# ctrl-pico.net
KiCad netlist of a schematic drawn in EAGLE
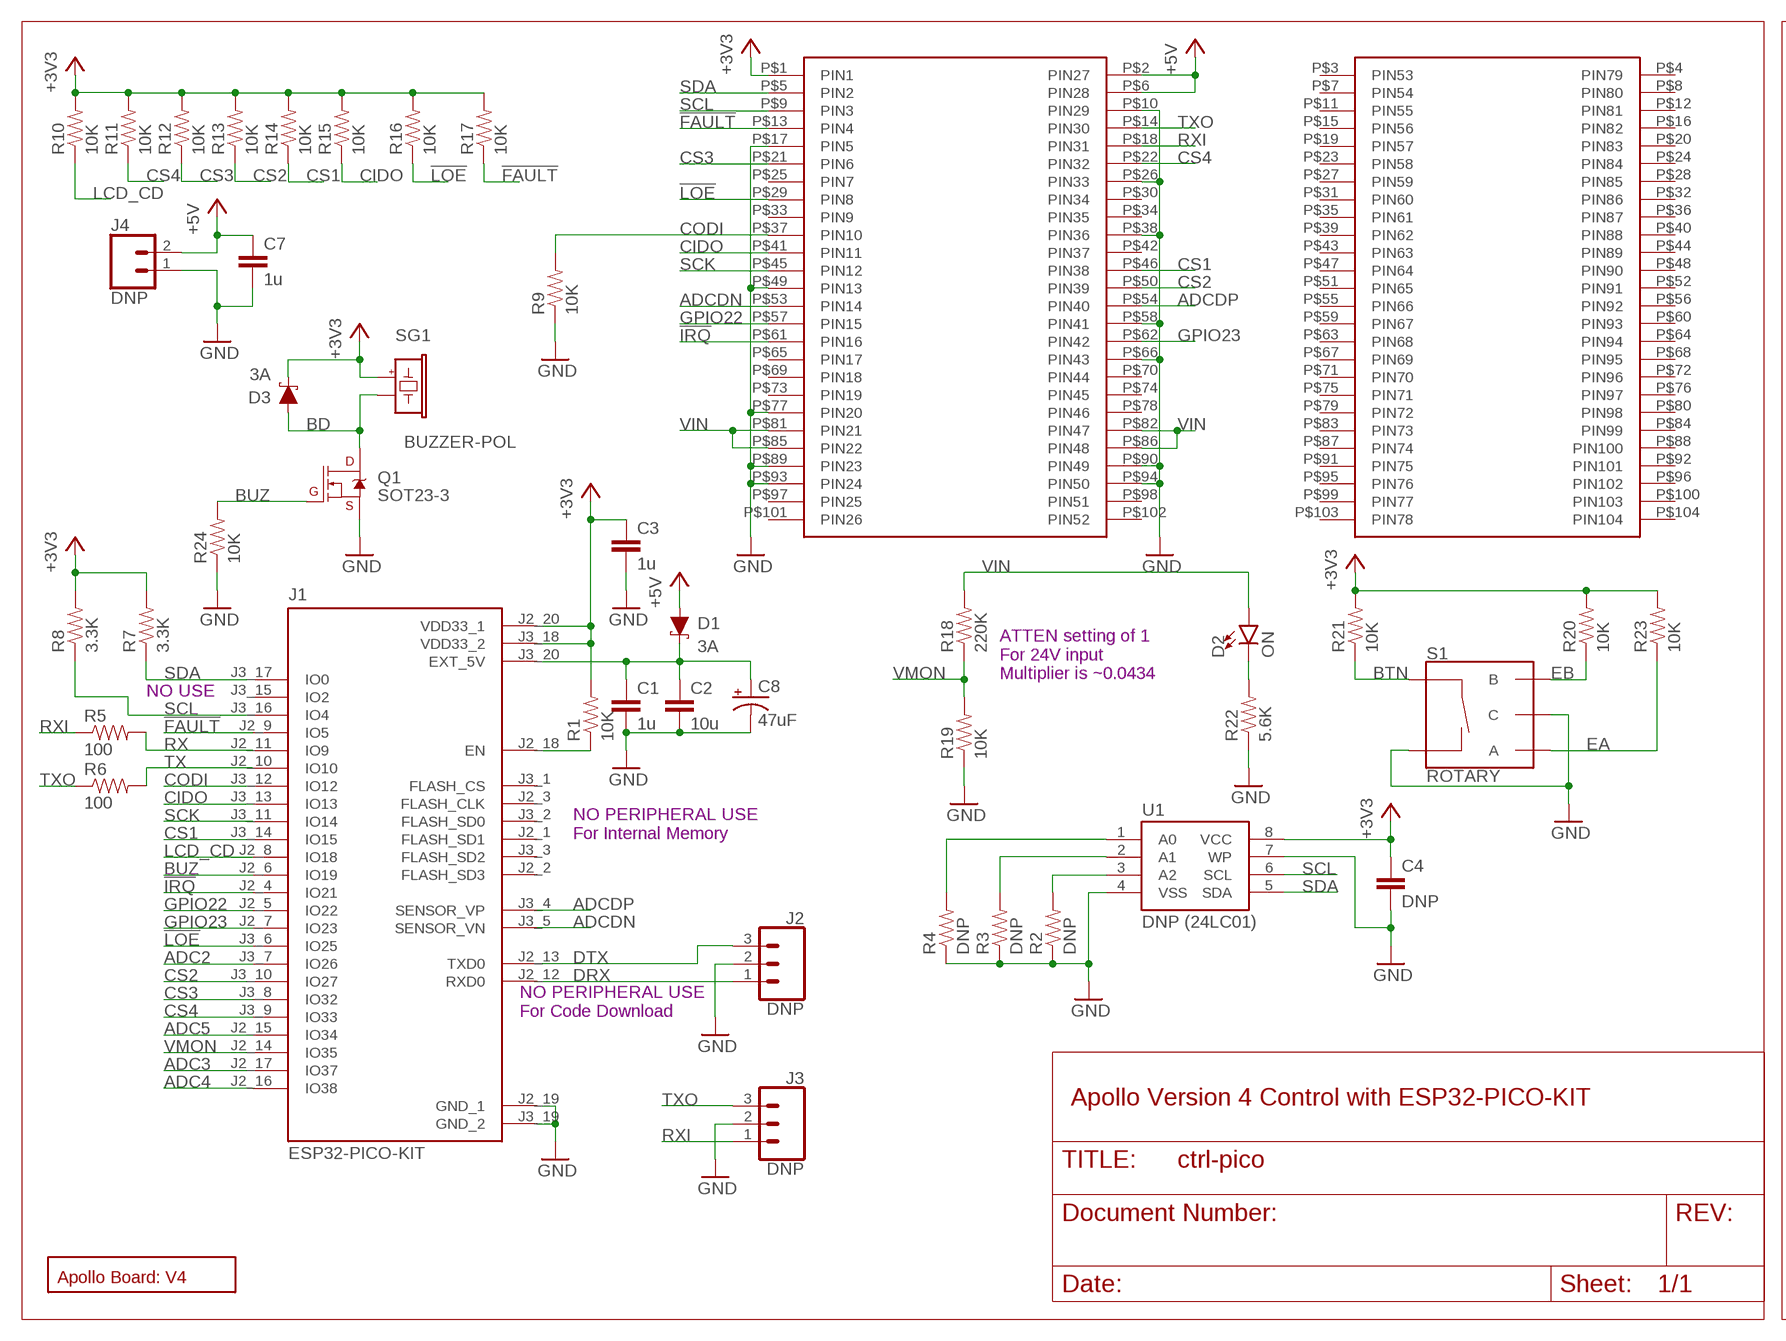
[diagram p0: schematic, sheet 1, part 1 of 2]
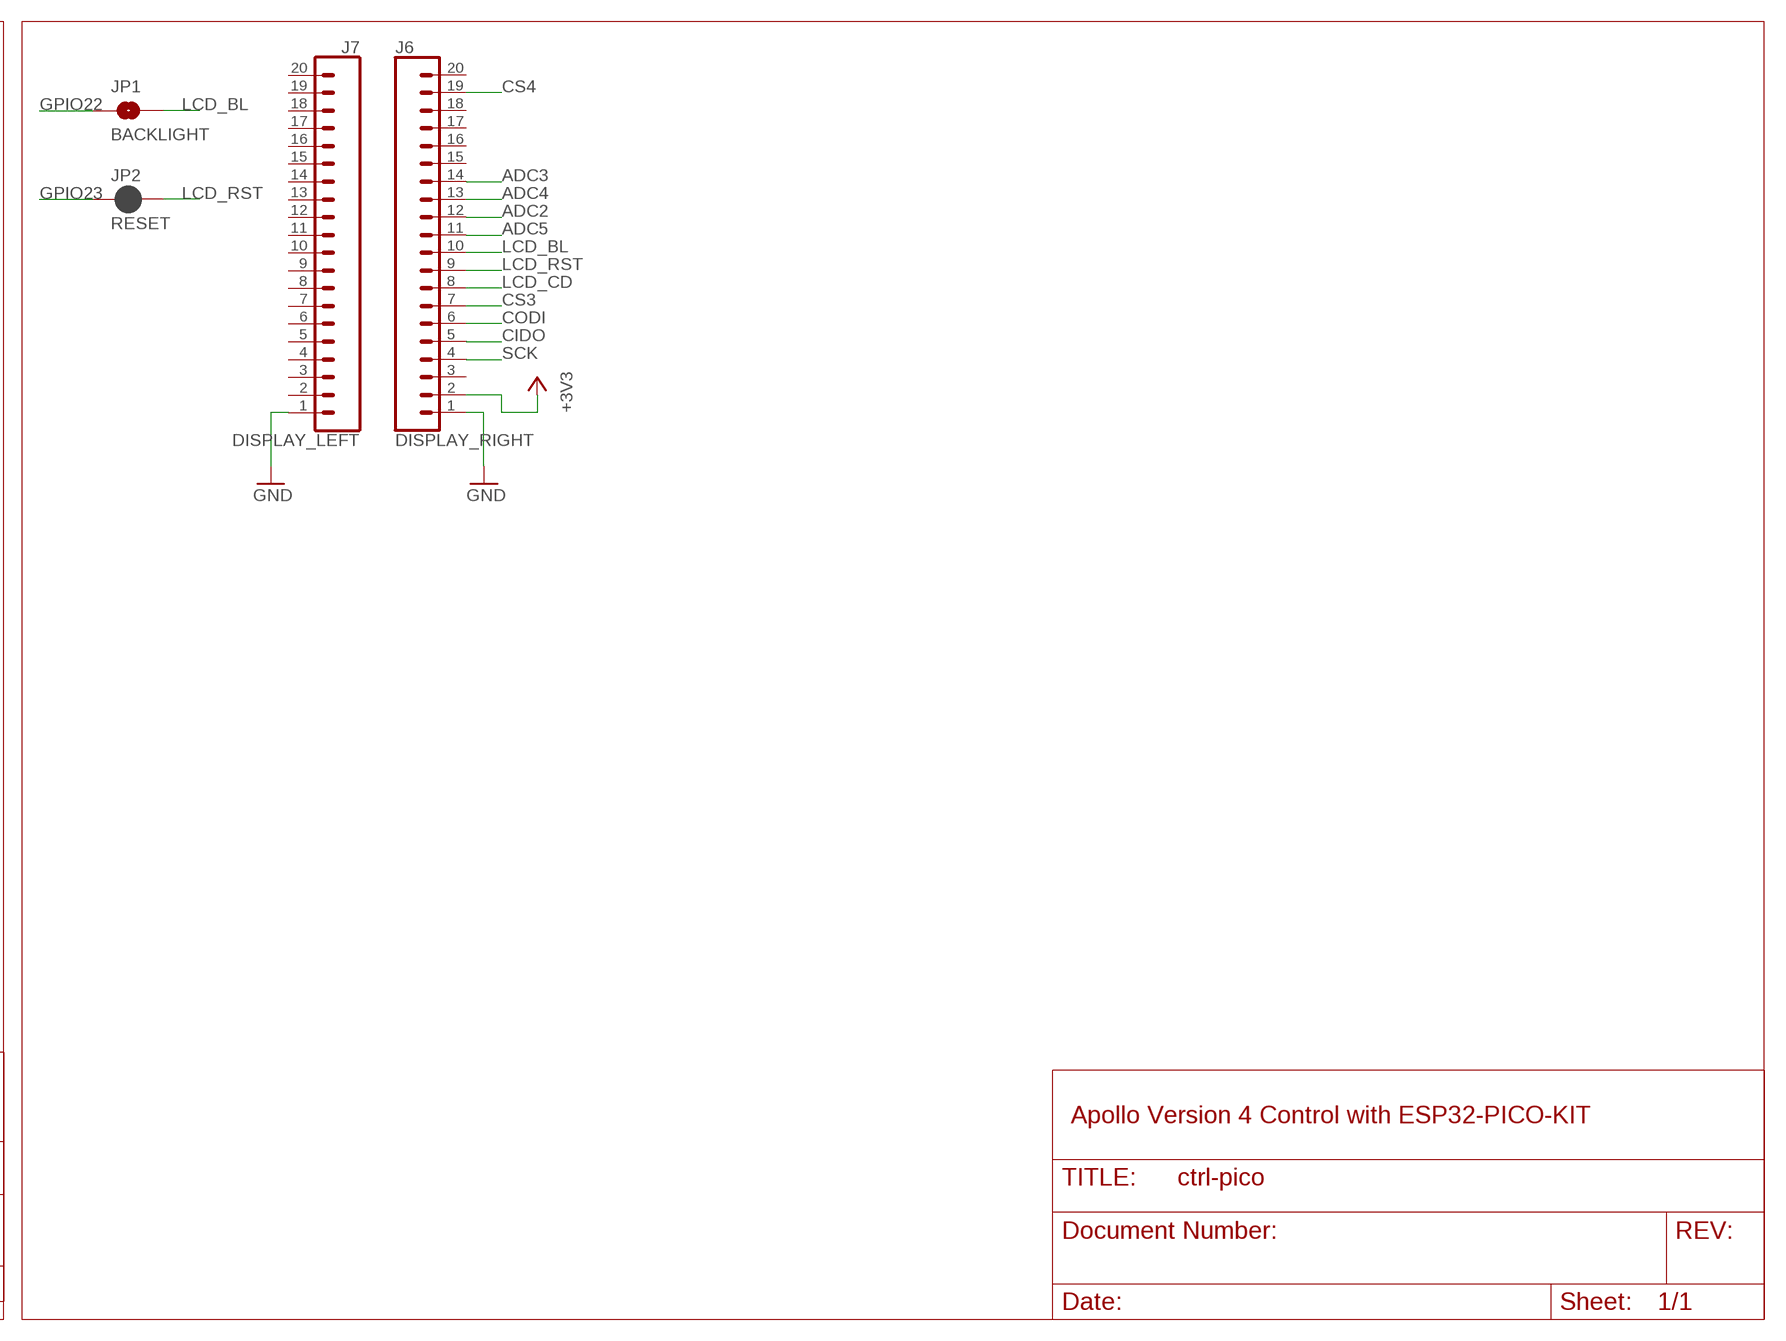
[diagram p1: schematic, sheet 1, part 2 of 2]

(export (version "E")
  (design (tool "Eeschema 10.0.6"))
  (components
    (comp (ref "C1")
      (value "1u")
      (footprint "eagle-import:0805")
      (libsource (lib "eagle-import") (part "CAP0805"))
    )
    (comp (ref "C2")
      (value "10u")
      (footprint "eagle-import:0805")
      (libsource (lib "eagle-import") (part "CAP0805"))
    )
    (comp (ref "C3")
      (value "1u")
      (footprint "eagle-import:0805")
      (libsource (lib "eagle-import") (part "CAP0805"))
    )
    (comp (ref "C4")
      (value "DNP")
      (footprint "eagle-import:0805")
      (libsource (lib "eagle-import") (part "CAP0805"))
    )
    (comp (ref "C7")
      (value "1u")
      (footprint "eagle-import:0805")
      (libsource (lib "eagle-import") (part "CAP0805"))
    )
    (comp (ref "C8")
      (value "47uF")
      (footprint "eagle-import:PANASONIC_D")
      (libsource (lib "eagle-import") (part "47UF-POLAR-PANASONIC_D-35V-20%"))
    )
    (comp (ref "D1")
      (value "3A")
      (footprint "eagle-import:SMA-DIODE")
      (libsource (lib "eagle-import") (part "DIODE-SCHOTTKY-B340A"))
    )
    (comp (ref "D2")
      (value "ON")
      (footprint "eagle-import:LED-0603")
      (libsource (lib "eagle-import") (part "LED-GREEN0603"))
    )
    (comp (ref "D3")
      (value "3A")
      (footprint "eagle-import:SMA-DIODE")
      (libsource (lib "eagle-import") (part "DIODE-SCHOTTKY-B340A"))
    )
    (comp (ref "J1")
      (value "ESP32-PICO-KIT")
      (footprint "eagle-import:XCVR_ESP32-PICO-KIT")
      (fields (field (name "DIGI-KEY_PART_NUMBER") "1965-1004-ND") (field (name "MF") "Espressif Systems"))
      (libsource (lib "eagle-import") (part "ESP32-PICO-KIT"))
    )
    (comp (ref "J2")
      (value "DNP")
      (footprint "eagle-import:1X03")
      (libsource (lib "eagle-import") (part "CONN_03"))
    )
    (comp (ref "J3")
      (value "DNP")
      (footprint "eagle-import:1X03")
      (libsource (lib "eagle-import") (part "CONN_03"))
    )
    (comp (ref "J4")
      (value "DNP")
      (footprint "eagle-import:1X02")
      (libsource (lib "eagle-import") (part "CONN_02"))
    )
    (comp (ref "J6")
      (value "DISPLAY_RIGHT")
      (footprint "eagle-import:1X20")
      (libsource (lib "eagle-import") (part "CONN_20"))
    )
    (comp (ref "J7")
      (value "DISPLAY_LEFT")
      (footprint "eagle-import:1X20")
      (libsource (lib "eagle-import") (part "CONN_20"))
    )
    (comp (ref "JP1")
      (value "BACKLIGHT")
      (footprint "eagle-import:SMT-JUMPER_2_NO_NO-SILK")
      (libsource (lib "eagle-import") (part "JUMPER-SMT_2_NO_NO-SILK"))
    )
    (comp (ref "JP2")
      (value "RESET")
      (footprint "eagle-import:SMT-JUMPER_2_NC_PASTE_NO-SILK")
      (libsource (lib "eagle-import") (part "JUMPER-SMT_2_NC_PASTE_NO-SILK"))
    )
    (comp (ref "Q1")
      (value "SOT23-3")
      (footprint "eagle-import:SOT23-3")
      (libsource (lib "eagle-import") (part "MOSFET-NCH-AO3404A"))
    )
    (comp (ref "R1")
      (value "10K")
      (footprint "eagle-import:0805")
      (libsource (lib "eagle-import") (part "RESISTOR0805-RES"))
    )
    (comp (ref "R2")
      (value "DNP")
      (footprint "eagle-import:0805")
      (libsource (lib "eagle-import") (part "RESISTOR0805-RES"))
    )
    (comp (ref "R3")
      (value "DNP")
      (footprint "eagle-import:0805")
      (libsource (lib "eagle-import") (part "RESISTOR0805-RES"))
    )
    (comp (ref "R4")
      (value "DNP")
      (footprint "eagle-import:0805")
      (libsource (lib "eagle-import") (part "RESISTOR0805-RES"))
    )
    (comp (ref "R5")
      (value "100")
      (footprint "eagle-import:0805")
      (libsource (lib "eagle-import") (part "RESISTOR0805-RES"))
    )
    (comp (ref "R6")
      (value "100")
      (footprint "eagle-import:0805")
      (libsource (lib "eagle-import") (part "RESISTOR0805-RES"))
    )
    (comp (ref "R7")
      (value "3.3K")
      (footprint "eagle-import:0805")
      (libsource (lib "eagle-import") (part "RESISTOR0805-RES"))
    )
    (comp (ref "R8")
      (value "3.3K")
      (footprint "eagle-import:0805")
      (libsource (lib "eagle-import") (part "RESISTOR0805-RES"))
    )
    (comp (ref "R9")
      (value "10K")
      (footprint "eagle-import:0805")
      (libsource (lib "eagle-import") (part "RESISTOR0805-RES"))
    )
    (comp (ref "R10")
      (value "10K")
      (footprint "eagle-import:0805")
      (libsource (lib "eagle-import") (part "RESISTOR0805-RES"))
    )
    (comp (ref "R11")
      (value "10K")
      (footprint "eagle-import:0805")
      (libsource (lib "eagle-import") (part "RESISTOR0805-RES"))
    )
    (comp (ref "R12")
      (value "10K")
      (footprint "eagle-import:0805")
      (libsource (lib "eagle-import") (part "RESISTOR0805-RES"))
    )
    (comp (ref "R13")
      (value "10K")
      (footprint "eagle-import:0805")
      (libsource (lib "eagle-import") (part "RESISTOR0805-RES"))
    )
    (comp (ref "R14")
      (value "10K")
      (footprint "eagle-import:0805")
      (libsource (lib "eagle-import") (part "RESISTOR0805-RES"))
    )
    (comp (ref "R15")
      (value "10K")
      (footprint "eagle-import:0805")
      (libsource (lib "eagle-import") (part "RESISTOR0805-RES"))
    )
    (comp (ref "R16")
      (value "10K")
      (footprint "eagle-import:0805")
      (libsource (lib "eagle-import") (part "RESISTOR0805-RES"))
    )
    (comp (ref "R17")
      (value "10K")
      (footprint "eagle-import:0805")
      (libsource (lib "eagle-import") (part "RESISTOR0805-RES"))
    )
    (comp (ref "R18")
      (value "220K")
      (footprint "eagle-import:0805")
      (libsource (lib "eagle-import") (part "RESISTOR0805-RES"))
    )
    (comp (ref "R19")
      (value "10K")
      (footprint "eagle-import:0805")
      (libsource (lib "eagle-import") (part "RESISTOR0805-RES"))
    )
    (comp (ref "R20")
      (value "10K")
      (footprint "eagle-import:0805")
      (libsource (lib "eagle-import") (part "RESISTOR0805-RES"))
    )
    (comp (ref "R21")
      (value "10K")
      (footprint "eagle-import:0805")
      (libsource (lib "eagle-import") (part "RESISTOR0805-RES"))
    )
    (comp (ref "R22")
      (value "5.6K")
      (footprint "eagle-import:0805")
      (libsource (lib "eagle-import") (part "RESISTOR0805-RES"))
    )
    (comp (ref "R23")
      (value "10K")
      (footprint "eagle-import:0805")
      (libsource (lib "eagle-import") (part "RESISTOR0805-RES"))
    )
    (comp (ref "R24")
      (value "10K")
      (footprint "eagle-import:0805")
      (libsource (lib "eagle-import") (part "RESISTOR0805-RES"))
    )
    (comp (ref "S1")
      (value "ROTARY")
      (footprint "eagle-import:ROTARY_ENC_PLAIN")
      (libsource (lib "eagle-import") (part "ENCODER-SWITCH"))
    )
    (comp (ref "SG1")
      (value "BUZZER-POL")
      (footprint "eagle-import:BUZZER-SMT-4")
      (libsource (lib "eagle-import") (part "BUZZER-POL"))
    )
    (comp (ref "U$1")
      (value "PC104_CONNECTOR")
      (footprint "eagle-import:PC104_CONNECTOR")
      (libsource (lib "eagle-import") (part "PC104_CONNECTOR"))
    )
    (comp (ref "U$2")
      (value "BOARD_TEMPLATE1")
      (footprint "eagle-import:BOARD_TEMPLATE")
      (libsource (lib "eagle-import") (part "BOARD_TEMPLATE1"))
    )
    (comp (ref "U1")
      (value "DNP (24LC01)")
      (footprint "eagle-import:SO08")
      (libsource (lib "eagle-import") (part "EEPROM-I2CSMD"))
    )
  )
  (nets
    (net (code "1") (name "+3V3") (class "Default")
      (node (ref "C3") (pin "1") (pinfunction "1_1") (pintype "passive"))
      (node (ref "C4") (pin "1") (pinfunction "1_1") (pintype "passive"))
      (node (ref "D3") (pin "C") (pinfunction "C_C") (pintype "passive"))
      (node (ref "J1") (pin "J2_20") (pinfunction "VDD33_1_J2_20") (pintype "power_in"))
      (node (ref "J1") (pin "J3_18") (pinfunction "VDD33_2_J3_18") (pintype "power_in"))
      (node (ref "J6") (pin "2") (pinfunction "2_2") (pintype "passive"))
      (node (ref "R1") (pin "2") (pinfunction "2_2") (pintype "passive"))
      (node (ref "R10") (pin "2") (pinfunction "2_2") (pintype "passive"))
      (node (ref "R11") (pin "2") (pinfunction "2_2") (pintype "passive"))
      (node (ref "R12") (pin "2") (pinfunction "2_2") (pintype "passive"))
      (node (ref "R13") (pin "2") (pinfunction "2_2") (pintype "passive"))
      (node (ref "R14") (pin "2") (pinfunction "2_2") (pintype "passive"))
      (node (ref "R15") (pin "2") (pinfunction "2_2") (pintype "passive"))
      (node (ref "R16") (pin "2") (pinfunction "2_2") (pintype "passive"))
      (node (ref "R17") (pin "2") (pinfunction "2_2") (pintype "passive"))
      (node (ref "R20") (pin "2") (pinfunction "2_2") (pintype "passive"))
      (node (ref "R21") (pin "2") (pinfunction "2_2") (pintype "passive"))
      (node (ref "R23") (pin "2") (pinfunction "2_2") (pintype "passive"))
      (node (ref "R7") (pin "2") (pinfunction "2_2") (pintype "passive"))
      (node (ref "R8") (pin "2") (pinfunction "2_2") (pintype "passive"))
      (node (ref "SG1") (pin "BP") (pinfunction "P_BP") (pintype "passive"))
      (node (ref "U$1") (pin "P$1") (pinfunction "PIN1_P$1") (pintype "bidirectional"))
      (node (ref "U1") (pin "8") (pinfunction "VCC_8") (pintype "power_in"))
    )
    (net (code "2") (name "+5V") (class "Default")
      (node (ref "C7") (pin "1") (pinfunction "1_1") (pintype "passive"))
      (node (ref "D1") (pin "A") (pinfunction "A_A") (pintype "passive"))
      (node (ref "J4") (pin "2") (pinfunction "2_2") (pintype "passive"))
      (node (ref "U$1") (pin "P$2") (pinfunction "PIN27_P$2") (pintype "bidirectional"))
      (node (ref "U$1") (pin "P$6") (pinfunction "PIN28_P$6") (pintype "bidirectional"))
    )
    (net (code "3") (name "/ADC2") (class "Default")
      (node (ref "J1") (pin "J3_7") (pinfunction "IO26_J3_7") (pintype "bidirectional"))
      (node (ref "J6") (pin "12") (pinfunction "12_12") (pintype "passive"))
    )
    (net (code "4") (name "/ADC3") (class "Default")
      (node (ref "J1") (pin "J2_17") (pinfunction "IO37_J2_17") (pintype "input"))
      (node (ref "J6") (pin "14") (pinfunction "14_14") (pintype "passive"))
    )
    (net (code "5") (name "/ADC4") (class "Default")
      (node (ref "J1") (pin "J2_16") (pinfunction "IO38_J2_16") (pintype "input"))
      (node (ref "J6") (pin "13") (pinfunction "13_13") (pintype "passive"))
    )
    (net (code "6") (name "/ADC5") (class "Default")
      (node (ref "J1") (pin "J2_15") (pinfunction "IO34_J2_15") (pintype "input"))
      (node (ref "J6") (pin "11") (pinfunction "11_11") (pintype "passive"))
    )
    (net (code "7") (name "/ADCDN") (class "Default")
      (node (ref "J1") (pin "J3_5") (pinfunction "SENSOR_VN_J3_5") (pintype "input"))
      (node (ref "U$1") (pin "P$53") (pinfunction "PIN14_P$53") (pintype "bidirectional"))
    )
    (net (code "8") (name "/ADCDP") (class "Default")
      (node (ref "J1") (pin "J3_4") (pinfunction "SENSOR_VP_J3_4") (pintype "input"))
      (node (ref "U$1") (pin "P$54") (pinfunction "PIN40_P$54") (pintype "bidirectional"))
    )
    (net (code "9") (name "/BD") (class "Default")
      (node (ref "D3") (pin "A") (pinfunction "A_A") (pintype "passive"))
      (node (ref "Q1") (pin "3") (pinfunction "D_3") (pintype "bidirectional"))
      (node (ref "SG1") (pin "BM") (pinfunction "N_BM") (pintype "passive"))
    )
    (net (code "10") (name "/BTN") (class "Default")
      (node (ref "R21") (pin "1") (pinfunction "1_1") (pintype "passive"))
      (node (ref "S1") (pin "SW+") (pinfunction "SW+_SW+") (pintype "bidirectional"))
    )
    (net (code "11") (name "/BUZ") (class "Default")
      (node (ref "J1") (pin "J2_6") (pinfunction "IO19_J2_6") (pintype "bidirectional"))
      (node (ref "Q1") (pin "1") (pinfunction "G_1") (pintype "bidirectional"))
      (node (ref "R24") (pin "2") (pinfunction "2_2") (pintype "passive"))
    )
    (net (code "12") (name "/CIDO") (class "Default")
      (node (ref "J1") (pin "J3_13") (pinfunction "IO13_J3_13") (pintype "bidirectional"))
      (node (ref "J6") (pin "5") (pinfunction "5_5") (pintype "passive"))
      (node (ref "R15") (pin "1") (pinfunction "1_1") (pintype "passive"))
      (node (ref "U$1") (pin "P$41") (pinfunction "PIN11_P$41") (pintype "bidirectional"))
    )
    (net (code "13") (name "/CODI") (class "Default")
      (node (ref "J1") (pin "J3_12") (pinfunction "IO12_J3_12") (pintype "bidirectional"))
      (node (ref "J6") (pin "6") (pinfunction "6_6") (pintype "passive"))
      (node (ref "R9") (pin "2") (pinfunction "2_2") (pintype "passive"))
      (node (ref "U$1") (pin "P$37") (pinfunction "PIN10_P$37") (pintype "bidirectional"))
    )
    (net (code "14") (name "/CS1") (class "Default")
      (node (ref "J1") (pin "J3_14") (pinfunction "IO15_J3_14") (pintype "bidirectional"))
      (node (ref "R14") (pin "1") (pinfunction "1_1") (pintype "passive"))
      (node (ref "U$1") (pin "P$46") (pinfunction "PIN38_P$46") (pintype "bidirectional"))
    )
    (net (code "15") (name "/CS2") (class "Default")
      (node (ref "J1") (pin "J3_10") (pinfunction "IO27_J3_10") (pintype "bidirectional"))
      (node (ref "R13") (pin "1") (pinfunction "1_1") (pintype "passive"))
      (node (ref "U$1") (pin "P$50") (pinfunction "PIN39_P$50") (pintype "bidirectional"))
    )
    (net (code "16") (name "/CS3") (class "Default")
      (node (ref "J1") (pin "J3_8") (pinfunction "IO32_J3_8") (pintype "bidirectional"))
      (node (ref "J6") (pin "7") (pinfunction "7_7") (pintype "passive"))
      (node (ref "R12") (pin "1") (pinfunction "1_1") (pintype "passive"))
      (node (ref "U$1") (pin "P$21") (pinfunction "PIN6_P$21") (pintype "bidirectional"))
    )
    (net (code "17") (name "/CS4") (class "Default")
      (node (ref "J1") (pin "J3_9") (pinfunction "IO33_J3_9") (pintype "bidirectional"))
      (node (ref "J6") (pin "19") (pinfunction "19_19") (pintype "passive"))
      (node (ref "R11") (pin "1") (pinfunction "1_1") (pintype "passive"))
      (node (ref "U$1") (pin "P$22") (pinfunction "PIN32_P$22") (pintype "bidirectional"))
    )
    (net (code "18") (name "/DRX") (class "Default")
      (node (ref "J1") (pin "J2_12") (pinfunction "RXD0_J2_12") (pintype "bidirectional"))
      (node (ref "J2") (pin "1") (pinfunction "1_1") (pintype "passive"))
    )
    (net (code "19") (name "/DTX") (class "Default")
      (node (ref "J1") (pin "J2_13") (pinfunction "TXD0_J2_13") (pintype "bidirectional"))
      (node (ref "J2") (pin "3") (pinfunction "3_3") (pintype "passive"))
    )
    (net (code "20") (name "/EA") (class "Default")
      (node (ref "R23") (pin "1") (pinfunction "1_1") (pintype "passive"))
      (node (ref "S1") (pin "A") (pinfunction "A_A") (pintype "bidirectional"))
    )
    (net (code "21") (name "/EB") (class "Default")
      (node (ref "R20") (pin "1") (pinfunction "1_1") (pintype "passive"))
      (node (ref "S1") (pin "B") (pinfunction "B_B") (pintype "bidirectional"))
    )
    (net (code "22") (name "/GPIO22") (class "Default")
      (node (ref "J1") (pin "J2_5") (pinfunction "IO22_J2_5") (pintype "bidirectional"))
      (node (ref "JP1") (pin "1") (pinfunction "1_1") (pintype "passive"))
      (node (ref "U$1") (pin "P$57") (pinfunction "PIN15_P$57") (pintype "bidirectional"))
    )
    (net (code "23") (name "/GPIO23") (class "Default")
      (node (ref "J1") (pin "J2_7") (pinfunction "IO23_J2_7") (pintype "bidirectional"))
      (node (ref "JP2") (pin "1") (pinfunction "1_1") (pintype "passive"))
      (node (ref "U$1") (pin "P$62") (pinfunction "PIN42_P$62") (pintype "bidirectional"))
    )
    (net (code "24") (name "/LCD_BL") (class "Default")
      (node (ref "J6") (pin "10") (pinfunction "10_10") (pintype "passive"))
      (node (ref "JP1") (pin "2") (pinfunction "2_2") (pintype "passive"))
    )
    (net (code "25") (name "/LCD_CD") (class "Default")
      (node (ref "J1") (pin "J2_8") (pinfunction "IO18_J2_8") (pintype "bidirectional"))
      (node (ref "J6") (pin "8") (pinfunction "8_8") (pintype "passive"))
      (node (ref "R10") (pin "1") (pinfunction "1_1") (pintype "passive"))
    )
    (net (code "26") (name "/LCD_RST") (class "Default")
      (node (ref "J6") (pin "9") (pinfunction "9_9") (pintype "passive"))
      (node (ref "JP2") (pin "2") (pinfunction "2_2") (pintype "passive"))
    )
    (net (code "27") (name "/RX") (class "Default")
      (node (ref "J1") (pin "J2_11") (pinfunction "IO9_J2_11") (pintype "bidirectional"))
      (node (ref "R5") (pin "2") (pinfunction "2_2") (pintype "passive"))
    )
    (net (code "28") (name "/RXI") (class "Default")
      (node (ref "J3") (pin "1") (pinfunction "1_1") (pintype "passive"))
      (node (ref "R5") (pin "1") (pinfunction "1_1") (pintype "passive"))
      (node (ref "U$1") (pin "P$18") (pinfunction "PIN31_P$18") (pintype "bidirectional"))
    )
    (net (code "29") (name "/SCK") (class "Default")
      (node (ref "J1") (pin "J3_11") (pinfunction "IO14_J3_11") (pintype "bidirectional"))
      (node (ref "J6") (pin "4") (pinfunction "4_4") (pintype "passive"))
      (node (ref "U$1") (pin "P$45") (pinfunction "PIN12_P$45") (pintype "bidirectional"))
    )
    (net (code "30") (name "/SCL") (class "Default")
      (node (ref "J1") (pin "J3_16") (pinfunction "IO4_J3_16") (pintype "bidirectional"))
      (node (ref "R8") (pin "1") (pinfunction "1_1") (pintype "passive"))
      (node (ref "U$1") (pin "P$9") (pinfunction "PIN3_P$9") (pintype "bidirectional"))
      (node (ref "U1") (pin "6") (pinfunction "SCL_6") (pintype "bidirectional"))
    )
    (net (code "31") (name "/SDA") (class "Default")
      (node (ref "J1") (pin "J3_17") (pinfunction "IO0_J3_17") (pintype "bidirectional"))
      (node (ref "R7") (pin "1") (pinfunction "1_1") (pintype "passive"))
      (node (ref "U$1") (pin "P$5") (pinfunction "PIN2_P$5") (pintype "bidirectional"))
      (node (ref "U1") (pin "5") (pinfunction "SDA_5") (pintype "bidirectional"))
    )
    (net (code "32") (name "/TX") (class "Default")
      (node (ref "J1") (pin "J2_10") (pinfunction "IO10_J2_10") (pintype "bidirectional"))
      (node (ref "R6") (pin "2") (pinfunction "2_2") (pintype "passive"))
    )
    (net (code "33") (name "/TXO") (class "Default")
      (node (ref "J3") (pin "3") (pinfunction "3_3") (pintype "passive"))
      (node (ref "R6") (pin "1") (pinfunction "1_1") (pintype "passive"))
      (node (ref "U$1") (pin "P$14") (pinfunction "PIN30_P$14") (pintype "bidirectional"))
    )
    (net (code "34") (name "/VIN") (class "Default")
      (node (ref "D2") (pin "A") (pinfunction "A_A") (pintype "passive"))
      (node (ref "R18") (pin "2") (pinfunction "2_2") (pintype "passive"))
      (node (ref "U$1") (pin "P$81") (pinfunction "PIN21_P$81") (pintype "bidirectional"))
      (node (ref "U$1") (pin "P$82") (pinfunction "PIN47_P$82") (pintype "bidirectional"))
      (node (ref "U$1") (pin "P$85") (pinfunction "PIN22_P$85") (pintype "bidirectional"))
      (node (ref "U$1") (pin "P$86") (pinfunction "PIN48_P$86") (pintype "bidirectional"))
    )
    (net (code "35") (name "/VMON") (class "Default")
      (node (ref "J1") (pin "J2_14") (pinfunction "IO35_J2_14") (pintype "input"))
      (node (ref "R18") (pin "1") (pinfunction "1_1") (pintype "passive"))
      (node (ref "R19") (pin "2") (pinfunction "2_2") (pintype "passive"))
    )
    (net (code "36") (name "/~{FAULT}") (class "Default")
      (node (ref "J1") (pin "J2_9") (pinfunction "IO5_J2_9") (pintype "bidirectional"))
      (node (ref "R17") (pin "1") (pinfunction "1_1") (pintype "passive"))
      (node (ref "U$1") (pin "P$13") (pinfunction "PIN4_P$13") (pintype "bidirectional"))
    )
    (net (code "37") (name "/~{IRQ}") (class "Default")
      (node (ref "J1") (pin "J2_4") (pinfunction "IO21_J2_4") (pintype "bidirectional"))
      (node (ref "U$1") (pin "P$61") (pinfunction "PIN16_P$61") (pintype "bidirectional"))
    )
    (net (code "38") (name "/~{LOE}") (class "Default")
      (node (ref "J1") (pin "J3_6") (pinfunction "IO25_J3_6") (pintype "bidirectional"))
      (node (ref "R16") (pin "1") (pinfunction "1_1") (pintype "passive"))
      (node (ref "U$1") (pin "P$29") (pinfunction "PIN8_P$29") (pintype "bidirectional"))
    )
    (net (code "39") (name "GND") (class "Default")
      (node (ref "C1") (pin "2") (pinfunction "2_2") (pintype "passive"))
      (node (ref "C2") (pin "2") (pinfunction "2_2") (pintype "passive"))
      (node (ref "C3") (pin "2") (pinfunction "2_2") (pintype "passive"))
      (node (ref "C4") (pin "2") (pinfunction "2_2") (pintype "passive"))
      (node (ref "C7") (pin "2") (pinfunction "2_2") (pintype "passive"))
      (node (ref "C8") (pin "-") (pinfunction "-_-") (pintype "passive"))
      (node (ref "J1") (pin "J2_19") (pinfunction "GND_1_J2_19") (pintype "power_in"))
      (node (ref "J1") (pin "J3_19") (pinfunction "GND_2_J3_19") (pintype "power_in"))
      (node (ref "J2") (pin "2") (pinfunction "2_2") (pintype "passive"))
      (node (ref "J3") (pin "2") (pinfunction "2_2") (pintype "passive"))
      (node (ref "J4") (pin "1") (pinfunction "1_1") (pintype "passive"))
      (node (ref "J6") (pin "1") (pinfunction "1_1") (pintype "passive"))
      (node (ref "J7") (pin "1") (pinfunction "1_1") (pintype "passive"))
      (node (ref "Q1") (pin "2") (pinfunction "S_2") (pintype "bidirectional"))
      (node (ref "R19") (pin "1") (pinfunction "1_1") (pintype "passive"))
      (node (ref "R2") (pin "1") (pinfunction "1_1") (pintype "passive"))
      (node (ref "R22") (pin "1") (pinfunction "1_1") (pintype "passive"))
      (node (ref "R24") (pin "1") (pinfunction "1_1") (pintype "passive"))
      (node (ref "R3") (pin "1") (pinfunction "1_1") (pintype "passive"))
      (node (ref "R4") (pin "1") (pinfunction "1_1") (pintype "passive"))
      (node (ref "R9") (pin "1") (pinfunction "1_1") (pintype "passive"))
      (node (ref "S1") (pin "C") (pinfunction "C_C") (pintype "bidirectional"))
      (node (ref "S1") (pin "SW-") (pinfunction "SW-_SW-") (pintype "bidirectional"))
      (node (ref "U$1") (pin "P$10") (pinfunction "PIN29_P$10") (pintype "bidirectional"))
      (node (ref "U$1") (pin "P$17") (pinfunction "PIN5_P$17") (pintype "bidirectional"))
      (node (ref "U$1") (pin "P$26") (pinfunction "PIN33_P$26") (pintype "bidirectional"))
      (node (ref "U$1") (pin "P$38") (pinfunction "PIN36_P$38") (pintype "bidirectional"))
      (node (ref "U$1") (pin "P$49") (pinfunction "PIN13_P$49") (pintype "bidirectional"))
      (node (ref "U$1") (pin "P$58") (pinfunction "PIN41_P$58") (pintype "bidirectional"))
      (node (ref "U$1") (pin "P$66") (pinfunction "PIN43_P$66") (pintype "bidirectional"))
      (node (ref "U$1") (pin "P$77") (pinfunction "PIN20_P$77") (pintype "bidirectional"))
      (node (ref "U$1") (pin "P$89") (pinfunction "PIN23_P$89") (pintype "bidirectional"))
      (node (ref "U$1") (pin "P$90") (pinfunction "PIN49_P$90") (pintype "bidirectional"))
      (node (ref "U$1") (pin "P$93") (pinfunction "PIN24_P$93") (pintype "bidirectional"))
      (node (ref "U$1") (pin "P$94") (pinfunction "PIN50_P$94") (pintype "bidirectional"))
      (node (ref "U1") (pin "4") (pinfunction "VSS_4") (pintype "power_in"))
      (node (ref "U1") (pin "7") (pinfunction "WP_7") (pintype "bidirectional"))
    )
    (net (code "40") (name "Net-(D2-PadC)") (class "Default")
      (node (ref "D2") (pin "C") (pinfunction "C_C") (pintype "passive"))
      (node (ref "R22") (pin "2") (pinfunction "2_2") (pintype "passive"))
    )
    (net (code "41") (name "Net-(J1-EN)") (class "Default")
      (node (ref "J1") (pin "J2_18") (pinfunction "EN_J2_18") (pintype "input"))
      (node (ref "R1") (pin "1") (pinfunction "1_1") (pintype "passive"))
    )
    (net (code "42") (name "Net-(J1-EXT_5V)") (class "Default")
      (node (ref "C1") (pin "1") (pinfunction "1_1") (pintype "passive"))
      (node (ref "C2") (pin "1") (pinfunction "1_1") (pintype "passive"))
      (node (ref "C8") (pin "+") (pinfunction "+_+") (pintype "passive"))
      (node (ref "D1") (pin "C") (pinfunction "C_C") (pintype "passive"))
      (node (ref "J1") (pin "J3_20") (pinfunction "EXT_5V_J3_20") (pintype "power_in"))
    )
    (net (code "43") (name "Net-(U1-A0)") (class "Default")
      (node (ref "R4") (pin "2") (pinfunction "2_2") (pintype "passive"))
      (node (ref "U1") (pin "1") (pinfunction "A0_1") (pintype "bidirectional"))
    )
    (net (code "44") (name "Net-(U1-A1)") (class "Default")
      (node (ref "R3") (pin "2") (pinfunction "2_2") (pintype "passive"))
      (node (ref "U1") (pin "2") (pinfunction "A1_2") (pintype "bidirectional"))
    )
    (net (code "45") (name "Net-(U1-A2)") (class "Default")
      (node (ref "R2") (pin "2") (pinfunction "2_2") (pintype "passive"))
      (node (ref "U1") (pin "3") (pinfunction "A2_3") (pintype "bidirectional"))
    )
    (net (code "46") (name "unconnected-(J1-FLASH_CLK-PadJ2_3)") (class "Default")
      (node (ref "J1") (pin "J2_3") (pinfunction "FLASH_CLK_J2_3") (pintype "bidirectional"))
    )
    (net (code "47") (name "unconnected-(J1-FLASH_CS-PadJ3_1)") (class "Default")
      (node (ref "J1") (pin "J3_1") (pinfunction "FLASH_CS_J3_1") (pintype "bidirectional"))
    )
    (net (code "48") (name "unconnected-(J1-FLASH_SD0-PadJ3_2)") (class "Default")
      (node (ref "J1") (pin "J3_2") (pinfunction "FLASH_SD0_J3_2") (pintype "bidirectional"))
    )
    (net (code "49") (name "unconnected-(J1-FLASH_SD1-PadJ2_1)") (class "Default")
      (node (ref "J1") (pin "J2_1") (pinfunction "FLASH_SD1_J2_1") (pintype "bidirectional"))
    )
    (net (code "50") (name "unconnected-(J1-FLASH_SD2-PadJ3_3)") (class "Default")
      (node (ref "J1") (pin "J3_3") (pinfunction "FLASH_SD2_J3_3") (pintype "bidirectional"))
    )
    (net (code "51") (name "unconnected-(J1-FLASH_SD3-PadJ2_2)") (class "Default")
      (node (ref "J1") (pin "J2_2") (pinfunction "FLASH_SD3_J2_2") (pintype "bidirectional"))
    )
    (net (code "52") (name "unconnected-(J1-IO2-PadJ3_15)") (class "Default")
      (node (ref "J1") (pin "J3_15") (pinfunction "IO2_J3_15") (pintype "bidirectional"))
    )
    (net (code "53") (name "unconnected-(J6-Pad3)") (class "Default")
      (node (ref "J6") (pin "3") (pinfunction "3_3") (pintype "passive"))
    )
    (net (code "54") (name "unconnected-(J6-Pad15)") (class "Default")
      (node (ref "J6") (pin "15") (pinfunction "15_15") (pintype "passive"))
    )
    (net (code "55") (name "unconnected-(J6-Pad16)") (class "Default")
      (node (ref "J6") (pin "16") (pinfunction "16_16") (pintype "passive"))
    )
    (net (code "56") (name "unconnected-(J6-Pad17)") (class "Default")
      (node (ref "J6") (pin "17") (pinfunction "17_17") (pintype "passive"))
    )
    (net (code "57") (name "unconnected-(J6-Pad18)") (class "Default")
      (node (ref "J6") (pin "18") (pinfunction "18_18") (pintype "passive"))
    )
    (net (code "58") (name "unconnected-(J6-Pad20)") (class "Default")
      (node (ref "J6") (pin "20") (pinfunction "20_20") (pintype "passive"))
    )
    (net (code "59") (name "unconnected-(J7-Pad2)") (class "Default")
      (node (ref "J7") (pin "2") (pinfunction "2_2") (pintype "passive"))
    )
    (net (code "60") (name "unconnected-(J7-Pad3)") (class "Default")
      (node (ref "J7") (pin "3") (pinfunction "3_3") (pintype "passive"))
    )
    (net (code "61") (name "unconnected-(J7-Pad4)") (class "Default")
      (node (ref "J7") (pin "4") (pinfunction "4_4") (pintype "passive"))
    )
    (net (code "62") (name "unconnected-(J7-Pad5)") (class "Default")
      (node (ref "J7") (pin "5") (pinfunction "5_5") (pintype "passive"))
    )
    (net (code "63") (name "unconnected-(J7-Pad6)") (class "Default")
      (node (ref "J7") (pin "6") (pinfunction "6_6") (pintype "passive"))
    )
    (net (code "64") (name "unconnected-(J7-Pad7)") (class "Default")
      (node (ref "J7") (pin "7") (pinfunction "7_7") (pintype "passive"))
    )
    (net (code "65") (name "unconnected-(J7-Pad8)") (class "Default")
      (node (ref "J7") (pin "8") (pinfunction "8_8") (pintype "passive"))
    )
    (net (code "66") (name "unconnected-(J7-Pad9)") (class "Default")
      (node (ref "J7") (pin "9") (pinfunction "9_9") (pintype "passive"))
    )
    (net (code "67") (name "unconnected-(J7-Pad10)") (class "Default")
      (node (ref "J7") (pin "10") (pinfunction "10_10") (pintype "passive"))
    )
    (net (code "68") (name "unconnected-(J7-Pad11)") (class "Default")
      (node (ref "J7") (pin "11") (pinfunction "11_11") (pintype "passive"))
    )
    (net (code "69") (name "unconnected-(J7-Pad12)") (class "Default")
      (node (ref "J7") (pin "12") (pinfunction "12_12") (pintype "passive"))
    )
    (net (code "70") (name "unconnected-(J7-Pad13)") (class "Default")
      (node (ref "J7") (pin "13") (pinfunction "13_13") (pintype "passive"))
    )
    (net (code "71") (name "unconnected-(J7-Pad14)") (class "Default")
      (node (ref "J7") (pin "14") (pinfunction "14_14") (pintype "passive"))
    )
    (net (code "72") (name "unconnected-(J7-Pad15)") (class "Default")
      (node (ref "J7") (pin "15") (pinfunction "15_15") (pintype "passive"))
    )
    (net (code "73") (name "unconnected-(J7-Pad16)") (class "Default")
      (node (ref "J7") (pin "16") (pinfunction "16_16") (pintype "passive"))
    )
    (net (code "74") (name "unconnected-(J7-Pad17)") (class "Default")
      (node (ref "J7") (pin "17") (pinfunction "17_17") (pintype "passive"))
    )
    (net (code "75") (name "unconnected-(J7-Pad18)") (class "Default")
      (node (ref "J7") (pin "18") (pinfunction "18_18") (pintype "passive"))
    )
    (net (code "76") (name "unconnected-(J7-Pad19)") (class "Default")
      (node (ref "J7") (pin "19") (pinfunction "19_19") (pintype "passive"))
    )
    (net (code "77") (name "unconnected-(J7-Pad20)") (class "Default")
      (node (ref "J7") (pin "20") (pinfunction "20_20") (pintype "passive"))
    )
    (net (code "78") (name "unconnected-(U$1-PIN7-PadP$25)") (class "Default")
      (node (ref "U$1") (pin "P$25") (pinfunction "PIN7_P$25") (pintype "bidirectional"))
    )
    (net (code "79") (name "unconnected-(U$1-PIN9-PadP$33)") (class "Default")
      (node (ref "U$1") (pin "P$33") (pinfunction "PIN9_P$33") (pintype "bidirectional"))
    )
    (net (code "80") (name "unconnected-(U$1-PIN17-PadP$65)") (class "Default")
      (node (ref "U$1") (pin "P$65") (pinfunction "PIN17_P$65") (pintype "bidirectional"))
    )
    (net (code "81") (name "unconnected-(U$1-PIN18-PadP$69)") (class "Default")
      (node (ref "U$1") (pin "P$69") (pinfunction "PIN18_P$69") (pintype "bidirectional"))
    )
    (net (code "82") (name "unconnected-(U$1-PIN19-PadP$73)") (class "Default")
      (node (ref "U$1") (pin "P$73") (pinfunction "PIN19_P$73") (pintype "bidirectional"))
    )
    (net (code "83") (name "unconnected-(U$1-PIN25-PadP$97)") (class "Default")
      (node (ref "U$1") (pin "P$97") (pinfunction "PIN25_P$97") (pintype "bidirectional"))
    )
    (net (code "84") (name "unconnected-(U$1-PIN26-PadP$101)") (class "Default")
      (node (ref "U$1") (pin "P$101") (pinfunction "PIN26_P$101") (pintype "bidirectional"))
    )
    (net (code "85") (name "unconnected-(U$1-PIN34-PadP$30)") (class "Default")
      (node (ref "U$1") (pin "P$30") (pinfunction "PIN34_P$30") (pintype "bidirectional"))
    )
    (net (code "86") (name "unconnected-(U$1-PIN35-PadP$34)") (class "Default")
      (node (ref "U$1") (pin "P$34") (pinfunction "PIN35_P$34") (pintype "bidirectional"))
    )
    (net (code "87") (name "unconnected-(U$1-PIN37-PadP$42)") (class "Default")
      (node (ref "U$1") (pin "P$42") (pinfunction "PIN37_P$42") (pintype "bidirectional"))
    )
    (net (code "88") (name "unconnected-(U$1-PIN44-PadP$70)") (class "Default")
      (node (ref "U$1") (pin "P$70") (pinfunction "PIN44_P$70") (pintype "bidirectional"))
    )
    (net (code "89") (name "unconnected-(U$1-PIN45-PadP$74)") (class "Default")
      (node (ref "U$1") (pin "P$74") (pinfunction "PIN45_P$74") (pintype "bidirectional"))
    )
    (net (code "90") (name "unconnected-(U$1-PIN46-PadP$78)") (class "Default")
      (node (ref "U$1") (pin "P$78") (pinfunction "PIN46_P$78") (pintype "bidirectional"))
    )
    (net (code "91") (name "unconnected-(U$1-PIN51-PadP$98)") (class "Default")
      (node (ref "U$1") (pin "P$98") (pinfunction "PIN51_P$98") (pintype "bidirectional"))
    )
    (net (code "92") (name "unconnected-(U$1-PIN52-PadP$102)") (class "Default")
      (node (ref "U$1") (pin "P$102") (pinfunction "PIN52_P$102") (pintype "bidirectional"))
    )
    (net (code "93") (name "unconnected-(U$1-PIN53-PadP$3)") (class "Default")
      (node (ref "U$1") (pin "P$3") (pinfunction "PIN53_P$3") (pintype "bidirectional"))
    )
    (net (code "94") (name "unconnected-(U$1-PIN54-PadP$7)") (class "Default")
      (node (ref "U$1") (pin "P$7") (pinfunction "PIN54_P$7") (pintype "bidirectional"))
    )
    (net (code "95") (name "unconnected-(U$1-PIN55-PadP$11)") (class "Default")
      (node (ref "U$1") (pin "P$11") (pinfunction "PIN55_P$11") (pintype "bidirectional"))
    )
    (net (code "96") (name "unconnected-(U$1-PIN56-PadP$15)") (class "Default")
      (node (ref "U$1") (pin "P$15") (pinfunction "PIN56_P$15") (pintype "bidirectional"))
    )
    (net (code "97") (name "unconnected-(U$1-PIN57-PadP$19)") (class "Default")
      (node (ref "U$1") (pin "P$19") (pinfunction "PIN57_P$19") (pintype "bidirectional"))
    )
    (net (code "98") (name "unconnected-(U$1-PIN58-PadP$23)") (class "Default")
      (node (ref "U$1") (pin "P$23") (pinfunction "PIN58_P$23") (pintype "bidirectional"))
    )
    (net (code "99") (name "unconnected-(U$1-PIN59-PadP$27)") (class "Default")
      (node (ref "U$1") (pin "P$27") (pinfunction "PIN59_P$27") (pintype "bidirectional"))
    )
    (net (code "100") (name "unconnected-(U$1-PIN60-PadP$31)") (class "Default")
      (node (ref "U$1") (pin "P$31") (pinfunction "PIN60_P$31") (pintype "bidirectional"))
    )
    (net (code "101") (name "unconnected-(U$1-PIN61-PadP$35)") (class "Default")
      (node (ref "U$1") (pin "P$35") (pinfunction "PIN61_P$35") (pintype "bidirectional"))
    )
    (net (code "102") (name "unconnected-(U$1-PIN62-PadP$39)") (class "Default")
      (node (ref "U$1") (pin "P$39") (pinfunction "PIN62_P$39") (pintype "bidirectional"))
    )
    (net (code "103") (name "unconnected-(U$1-PIN63-PadP$43)") (class "Default")
      (node (ref "U$1") (pin "P$43") (pinfunction "PIN63_P$43") (pintype "bidirectional"))
    )
    (net (code "104") (name "unconnected-(U$1-PIN64-PadP$47)") (class "Default")
      (node (ref "U$1") (pin "P$47") (pinfunction "PIN64_P$47") (pintype "bidirectional"))
    )
    (net (code "105") (name "unconnected-(U$1-PIN65-PadP$51)") (class "Default")
      (node (ref "U$1") (pin "P$51") (pinfunction "PIN65_P$51") (pintype "bidirectional"))
    )
    (net (code "106") (name "unconnected-(U$1-PIN66-PadP$55)") (class "Default")
      (node (ref "U$1") (pin "P$55") (pinfunction "PIN66_P$55") (pintype "bidirectional"))
    )
    (net (code "107") (name "unconnected-(U$1-PIN67-PadP$59)") (class "Default")
      (node (ref "U$1") (pin "P$59") (pinfunction "PIN67_P$59") (pintype "bidirectional"))
    )
    (net (code "108") (name "unconnected-(U$1-PIN68-PadP$63)") (class "Default")
      (node (ref "U$1") (pin "P$63") (pinfunction "PIN68_P$63") (pintype "bidirectional"))
    )
    (net (code "109") (name "unconnected-(U$1-PIN69-PadP$67)") (class "Default")
      (node (ref "U$1") (pin "P$67") (pinfunction "PIN69_P$67") (pintype "bidirectional"))
    )
    (net (code "110") (name "unconnected-(U$1-PIN70-PadP$71)") (class "Default")
      (node (ref "U$1") (pin "P$71") (pinfunction "PIN70_P$71") (pintype "bidirectional"))
    )
    (net (code "111") (name "unconnected-(U$1-PIN71-PadP$75)") (class "Default")
      (node (ref "U$1") (pin "P$75") (pinfunction "PIN71_P$75") (pintype "bidirectional"))
    )
    (net (code "112") (name "unconnected-(U$1-PIN72-PadP$79)") (class "Default")
      (node (ref "U$1") (pin "P$79") (pinfunction "PIN72_P$79") (pintype "bidirectional"))
    )
    (net (code "113") (name "unconnected-(U$1-PIN73-PadP$83)") (class "Default")
      (node (ref "U$1") (pin "P$83") (pinfunction "PIN73_P$83") (pintype "bidirectional"))
    )
    (net (code "114") (name "unconnected-(U$1-PIN74-PadP$87)") (class "Default")
      (node (ref "U$1") (pin "P$87") (pinfunction "PIN74_P$87") (pintype "bidirectional"))
    )
    (net (code "115") (name "unconnected-(U$1-PIN75-PadP$91)") (class "Default")
      (node (ref "U$1") (pin "P$91") (pinfunction "PIN75_P$91") (pintype "bidirectional"))
    )
    (net (code "116") (name "unconnected-(U$1-PIN76-PadP$95)") (class "Default")
      (node (ref "U$1") (pin "P$95") (pinfunction "PIN76_P$95") (pintype "bidirectional"))
    )
    (net (code "117") (name "unconnected-(U$1-PIN77-PadP$99)") (class "Default")
      (node (ref "U$1") (pin "P$99") (pinfunction "PIN77_P$99") (pintype "bidirectional"))
    )
    (net (code "118") (name "unconnected-(U$1-PIN78-PadP$103)") (class "Default")
      (node (ref "U$1") (pin "P$103") (pinfunction "PIN78_P$103") (pintype "bidirectional"))
    )
    (net (code "119") (name "unconnected-(U$1-PIN79-PadP$4)") (class "Default")
      (node (ref "U$1") (pin "P$4") (pinfunction "PIN79_P$4") (pintype "bidirectional"))
    )
    (net (code "120") (name "unconnected-(U$1-PIN80-PadP$8)") (class "Default")
      (node (ref "U$1") (pin "P$8") (pinfunction "PIN80_P$8") (pintype "bidirectional"))
    )
    (net (code "121") (name "unconnected-(U$1-PIN81-PadP$12)") (class "Default")
      (node (ref "U$1") (pin "P$12") (pinfunction "PIN81_P$12") (pintype "bidirectional"))
    )
    (net (code "122") (name "unconnected-(U$1-PIN82-PadP$16)") (class "Default")
      (node (ref "U$1") (pin "P$16") (pinfunction "PIN82_P$16") (pintype "bidirectional"))
    )
    (net (code "123") (name "unconnected-(U$1-PIN83-PadP$20)") (class "Default")
      (node (ref "U$1") (pin "P$20") (pinfunction "PIN83_P$20") (pintype "bidirectional"))
    )
    (net (code "124") (name "unconnected-(U$1-PIN84-PadP$24)") (class "Default")
      (node (ref "U$1") (pin "P$24") (pinfunction "PIN84_P$24") (pintype "bidirectional"))
    )
    (net (code "125") (name "unconnected-(U$1-PIN85-PadP$28)") (class "Default")
      (node (ref "U$1") (pin "P$28") (pinfunction "PIN85_P$28") (pintype "bidirectional"))
    )
    (net (code "126") (name "unconnected-(U$1-PIN86-PadP$32)") (class "Default")
      (node (ref "U$1") (pin "P$32") (pinfunction "PIN86_P$32") (pintype "bidirectional"))
    )
    (net (code "127") (name "unconnected-(U$1-PIN87-PadP$36)") (class "Default")
      (node (ref "U$1") (pin "P$36") (pinfunction "PIN87_P$36") (pintype "bidirectional"))
    )
    (net (code "128") (name "unconnected-(U$1-PIN88-PadP$40)") (class "Default")
      (node (ref "U$1") (pin "P$40") (pinfunction "PIN88_P$40") (pintype "bidirectional"))
    )
    (net (code "129") (name "unconnected-(U$1-PIN89-PadP$44)") (class "Default")
      (node (ref "U$1") (pin "P$44") (pinfunction "PIN89_P$44") (pintype "bidirectional"))
    )
    (net (code "130") (name "unconnected-(U$1-PIN90-PadP$48)") (class "Default")
      (node (ref "U$1") (pin "P$48") (pinfunction "PIN90_P$48") (pintype "bidirectional"))
    )
    (net (code "131") (name "unconnected-(U$1-PIN91-PadP$52)") (class "Default")
      (node (ref "U$1") (pin "P$52") (pinfunction "PIN91_P$52") (pintype "bidirectional"))
    )
    (net (code "132") (name "unconnected-(U$1-PIN92-PadP$56)") (class "Default")
      (node (ref "U$1") (pin "P$56") (pinfunction "PIN92_P$56") (pintype "bidirectional"))
    )
    (net (code "133") (name "unconnected-(U$1-PIN93-PadP$60)") (class "Default")
      (node (ref "U$1") (pin "P$60") (pinfunction "PIN93_P$60") (pintype "bidirectional"))
    )
    (net (code "134") (name "unconnected-(U$1-PIN94-PadP$64)") (class "Default")
      (node (ref "U$1") (pin "P$64") (pinfunction "PIN94_P$64") (pintype "bidirectional"))
    )
    (net (code "135") (name "unconnected-(U$1-PIN95-PadP$68)") (class "Default")
      (node (ref "U$1") (pin "P$68") (pinfunction "PIN95_P$68") (pintype "bidirectional"))
    )
    (net (code "136") (name "unconnected-(U$1-PIN96-PadP$72)") (class "Default")
      (node (ref "U$1") (pin "P$72") (pinfunction "PIN96_P$72") (pintype "bidirectional"))
    )
    (net (code "137") (name "unconnected-(U$1-PIN97-PadP$76)") (class "Default")
      (node (ref "U$1") (pin "P$76") (pinfunction "PIN97_P$76") (pintype "bidirectional"))
    )
    (net (code "138") (name "unconnected-(U$1-PIN98-PadP$80)") (class "Default")
      (node (ref "U$1") (pin "P$80") (pinfunction "PIN98_P$80") (pintype "bidirectional"))
    )
    (net (code "139") (name "unconnected-(U$1-PIN99-PadP$84)") (class "Default")
      (node (ref "U$1") (pin "P$84") (pinfunction "PIN99_P$84") (pintype "bidirectional"))
    )
    (net (code "140") (name "unconnected-(U$1-PIN100-PadP$88)") (class "Default")
      (node (ref "U$1") (pin "P$88") (pinfunction "PIN100_P$88") (pintype "bidirectional"))
    )
    (net (code "141") (name "unconnected-(U$1-PIN101-PadP$92)") (class "Default")
      (node (ref "U$1") (pin "P$92") (pinfunction "PIN101_P$92") (pintype "bidirectional"))
    )
    (net (code "142") (name "unconnected-(U$1-PIN102-PadP$96)") (class "Default")
      (node (ref "U$1") (pin "P$96") (pinfunction "PIN102_P$96") (pintype "bidirectional"))
    )
    (net (code "143") (name "unconnected-(U$1-PIN103-PadP$100)") (class "Default")
      (node (ref "U$1") (pin "P$100") (pinfunction "PIN103_P$100") (pintype "bidirectional"))
    )
    (net (code "144") (name "unconnected-(U$1-PIN104-PadP$104)") (class "Default")
      (node (ref "U$1") (pin "P$104") (pinfunction "PIN104_P$104") (pintype "bidirectional"))
    )
  )
)
